# 00-eagleClass-01-battery-leds.net
KiCad netlist of a schematic drawn in EAGLE
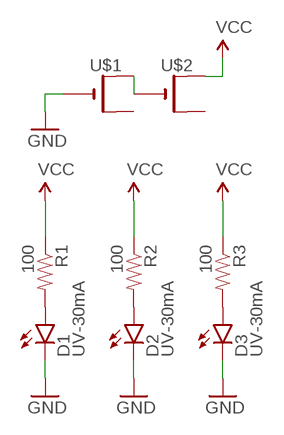
[diagram p0: schematic, sheet 1]

(export (version "E")
  (design (tool "Eeschema 10.0.6"))
  (components
    (comp (ref "D1")
      (value "UV-30mA")
      (footprint "eagle-import:LED5MM")
      (libsource (lib "eagle-import") (part "LED5MM"))
    )
    (comp (ref "D2")
      (value "UV-30mA")
      (footprint "eagle-import:LED5MM")
      (libsource (lib "eagle-import") (part "LED5MM"))
    )
    (comp (ref "D3")
      (value "UV-30mA")
      (footprint "eagle-import:LED5MM")
      (libsource (lib "eagle-import") (part "LED5MM"))
    )
    (comp (ref "R1")
      (value "100")
      (footprint "eagle-import:AXIAL-0.3EZ")
      (libsource (lib "eagle-import") (part "1KOHM-1/4W-5%(PTH)HORIZ-KIT"))
    )
    (comp (ref "R2")
      (value "100")
      (footprint "eagle-import:AXIAL-0.3EZ")
      (libsource (lib "eagle-import") (part "1KOHM-1/4W-5%(PTH)HORIZ-KIT"))
    )
    (comp (ref "R3")
      (value "100")
      (footprint "eagle-import:AXIAL-0.3EZ")
      (libsource (lib "eagle-import") (part "1KOHM-1/4W-5%(PTH)HORIZ-KIT"))
    )
    (comp (ref "U$1")
      (value "CR2032THM")
      (footprint "eagle-import:CR2032-THRU")
      (libsource (lib "eagle-import") (part "CR2032THM"))
    )
    (comp (ref "U$2")
      (value "CR2032THM")
      (footprint "eagle-import:CR2032-THRU")
      (libsource (lib "eagle-import") (part "CR2032THM"))
    )
  )
  (nets
    (net (code "1") (name "GND") (class "Default")
      (node (ref "D1") (pin "K") (pinfunction "C_K") (pintype "passive"))
      (node (ref "D2") (pin "K") (pinfunction "C_K") (pintype "passive"))
      (node (ref "D3") (pin "K") (pinfunction "C_K") (pintype "passive"))
      (node (ref "U$1") (pin "-") (pinfunction "-_-") (pintype "passive"))
    )
    (net (code "2") (name "Net-(R1-2)") (class "Default")
      (node (ref "D1") (pin "A") (pinfunction "A_A") (pintype "passive"))
      (node (ref "R1") (pin "P$2") (pinfunction "2_P$2") (pintype "passive"))
    )
    (net (code "3") (name "Net-(R2-2)") (class "Default")
      (node (ref "D2") (pin "A") (pinfunction "A_A") (pintype "passive"))
      (node (ref "R2") (pin "P$2") (pinfunction "2_P$2") (pintype "passive"))
    )
    (net (code "4") (name "Net-(R3-2)") (class "Default")
      (node (ref "D3") (pin "A") (pinfunction "A_A") (pintype "passive"))
      (node (ref "R3") (pin "P$2") (pinfunction "2_P$2") (pintype "passive"))
    )
    (net (code "5") (name "Net-(U$1-+)") (class "Default")
      (node (ref "U$1") (pin "+1") (pinfunction "+_+1") (pintype "passive"))
      (node (ref "U$2") (pin "-") (pinfunction "-_-") (pintype "passive"))
    )
    (net (code "6") (name "VCC") (class "Default")
      (node (ref "R1") (pin "P$1") (pinfunction "1_P$1") (pintype "passive"))
      (node (ref "R2") (pin "P$1") (pinfunction "1_P$1") (pintype "passive"))
      (node (ref "R3") (pin "P$1") (pinfunction "1_P$1") (pintype "passive"))
      (node (ref "U$2") (pin "+1") (pinfunction "+_+1") (pintype "passive"))
    )
    (net (code "7") (name "unconnected-(U$1-+1-Pad+2)") (class "Default")
      (node (ref "U$1") (pin "+2") (pinfunction "+1_+2") (pintype "passive"))
    )
    (net (code "8") (name "unconnected-(U$2-+1-Pad+2)") (class "Default")
      (node (ref "U$2") (pin "+2") (pinfunction "+1_+2") (pintype "passive"))
    )
  )
)
